# New_Schematic.net
KiCad netlist of a schematic drawn in EAGLE
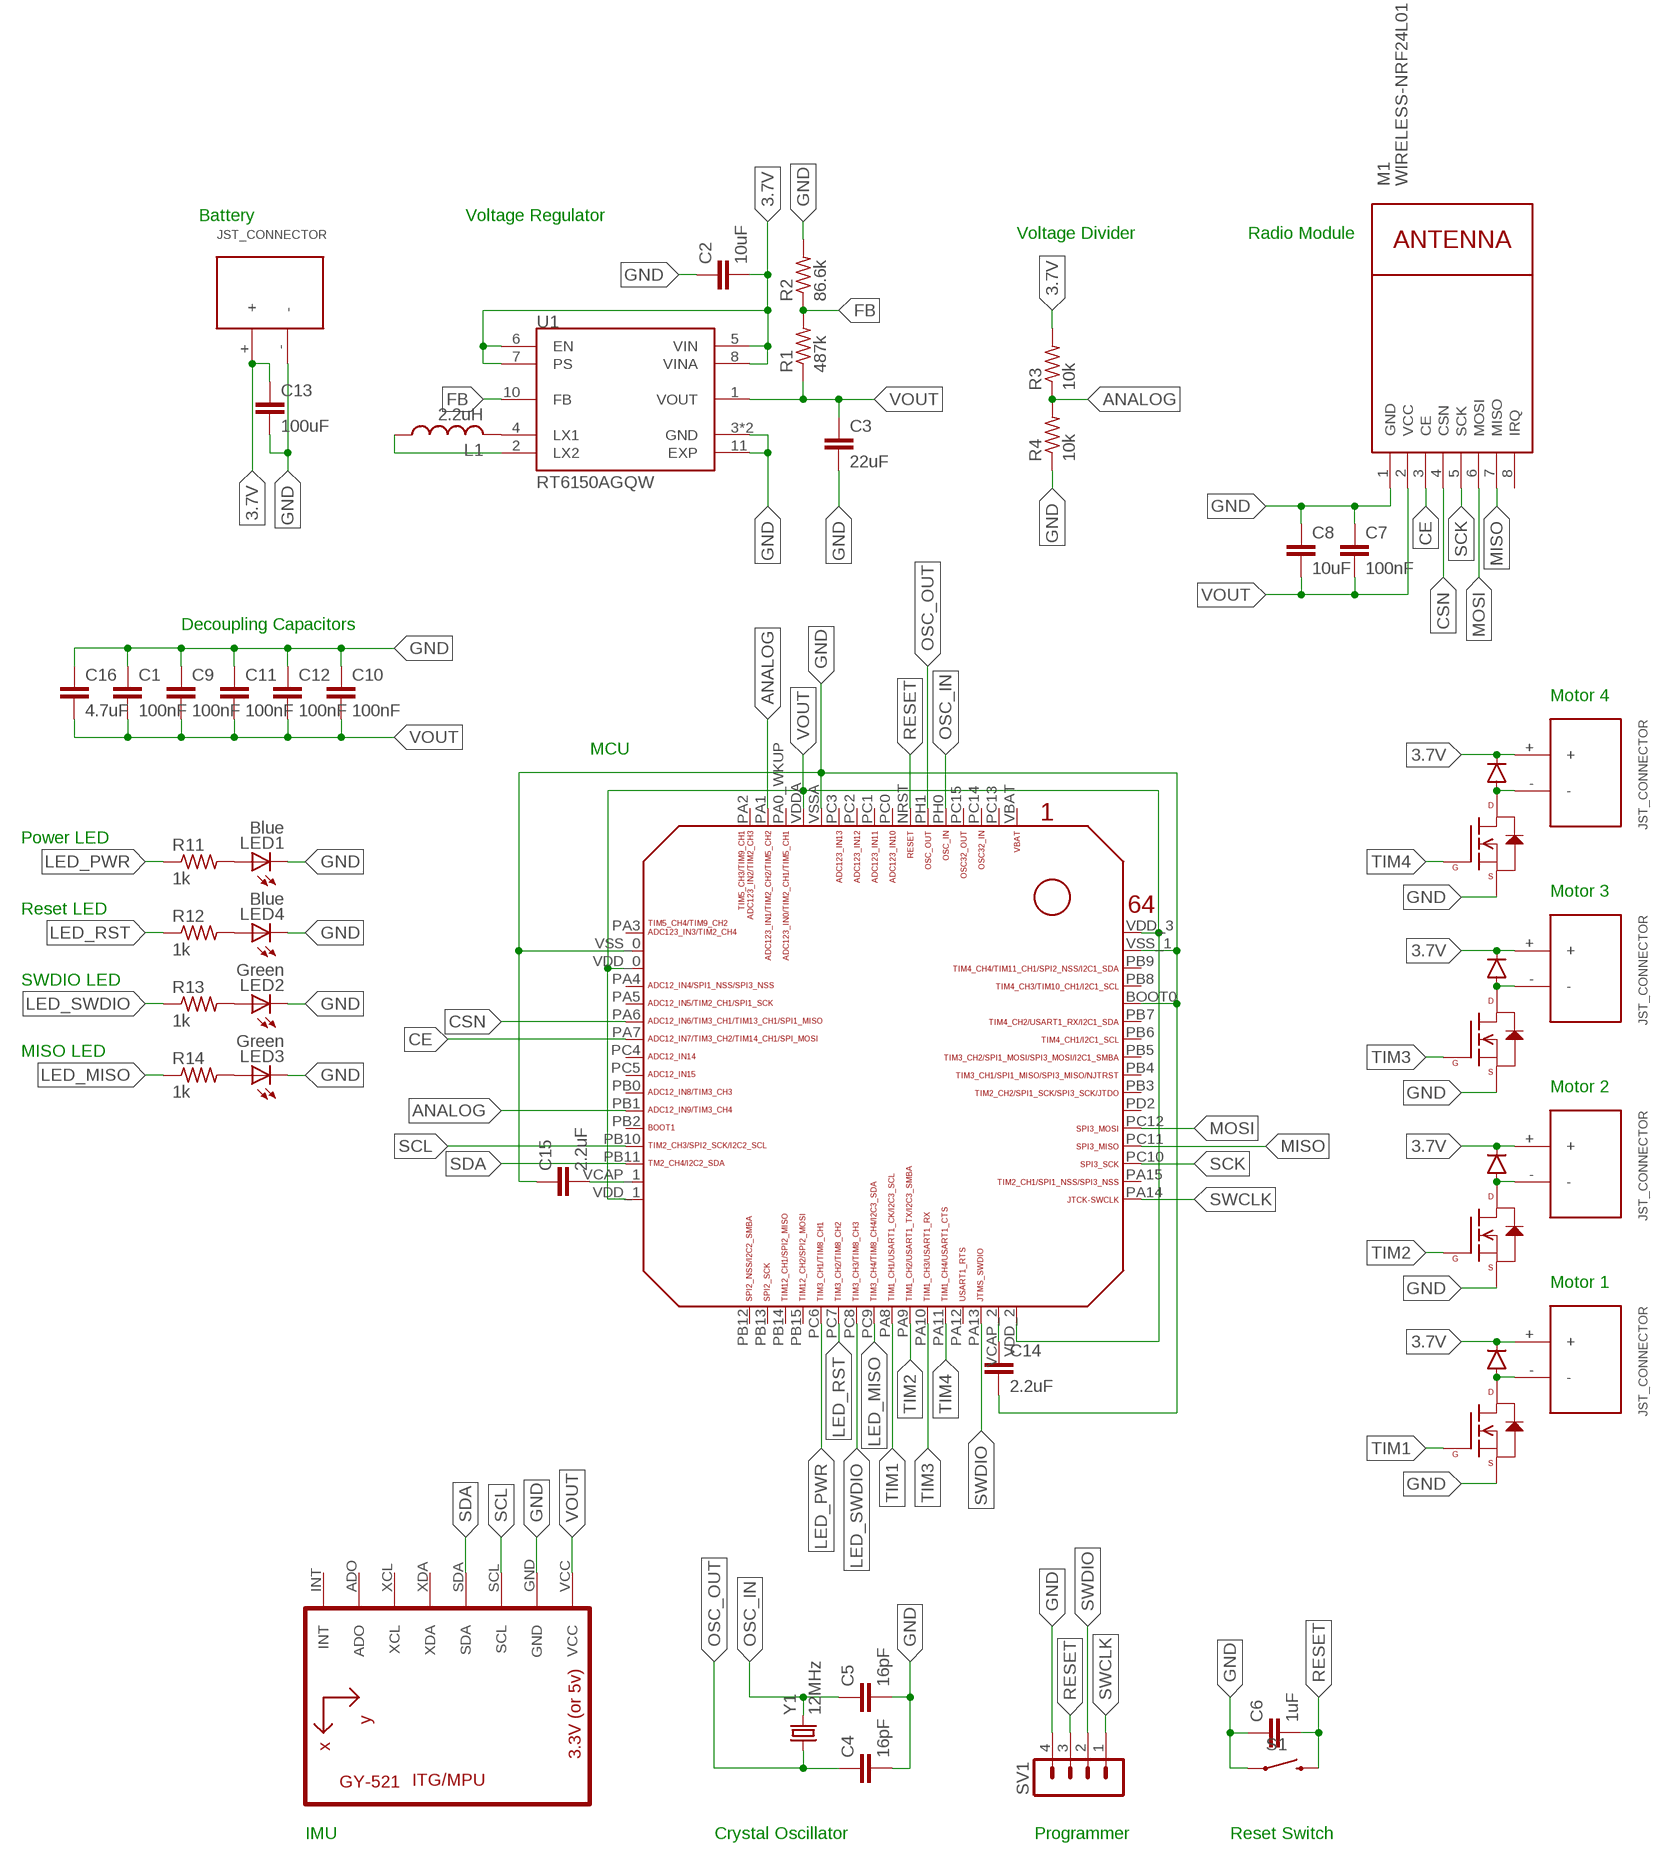
[diagram p0: schematic, sheet 1]

(export (version "E")
  (design (tool "Eeschema 10.0.6"))
  (components
    (comp (ref "C1")
      (value "100nF")
      (footprint "eagle-import:C0603")
      (libsource (lib "eagle-import") (part "rcl_334_C-EUC0603"))
    )
    (comp (ref "C2")
      (value "10uF")
      (footprint "eagle-import:C0603")
      (libsource (lib "eagle-import") (part "rcl_334_C-EUC0603"))
    )
    (comp (ref "C3")
      (value "22uF")
      (footprint "eagle-import:C0603")
      (libsource (lib "eagle-import") (part "rcl_334_C-EUC0603"))
    )
    (comp (ref "C4")
      (value "16pF")
      (footprint "eagle-import:C0603")
      (libsource (lib "eagle-import") (part "rcl_334_C-EUC0603"))
    )
    (comp (ref "C5")
      (value "16pF")
      (footprint "eagle-import:C0603")
      (libsource (lib "eagle-import") (part "rcl_334_C-EUC0603"))
    )
    (comp (ref "C6")
      (value "1uF")
      (footprint "eagle-import:C0603")
      (libsource (lib "eagle-import") (part "rcl_334_C-EUC0603"))
    )
    (comp (ref "C7")
      (value "100nF")
      (footprint "eagle-import:C0603")
      (libsource (lib "eagle-import") (part "rcl_334_C-EUC0603"))
    )
    (comp (ref "C8")
      (value "10uF")
      (footprint "eagle-import:C0603")
      (libsource (lib "eagle-import") (part "rcl_334_C-EUC0603"))
    )
    (comp (ref "C9")
      (value "100nF")
      (footprint "eagle-import:C0603")
      (libsource (lib "eagle-import") (part "rcl_334_C-EUC0603"))
    )
    (comp (ref "C10")
      (value "100nF")
      (footprint "eagle-import:C0603")
      (libsource (lib "eagle-import") (part "rcl_334_C-EUC0603"))
    )
    (comp (ref "C11")
      (value "100nF")
      (footprint "eagle-import:C0603")
      (libsource (lib "eagle-import") (part "rcl_334_C-EUC0603"))
    )
    (comp (ref "C12")
      (value "100nF")
      (footprint "eagle-import:C0603")
      (libsource (lib "eagle-import") (part "rcl_334_C-EUC0603"))
    )
    (comp (ref "C13")
      (value "100uF")
      (footprint "eagle-import:C1206")
      (libsource (lib "eagle-import") (part "rcl_334_C-EUC1206"))
    )
    (comp (ref "C14")
      (value "2.2uF")
      (footprint "eagle-import:C0603")
      (libsource (lib "eagle-import") (part "C-EUC0603"))
    )
    (comp (ref "C15")
      (value "2.2uF")
      (footprint "eagle-import:C0603")
      (libsource (lib "eagle-import") (part "C-EUC0603"))
    )
    (comp (ref "C16")
      (value "4.7uF")
      (footprint "eagle-import:C0603")
      (libsource (lib "eagle-import") (part "rcl_334_C-EUC0603"))
    )
    (comp (ref "L1")
      (value "2.2uH")
      (footprint "eagle-import:L0603")
      (libsource (lib "eagle-import") (part "L-USL0603"))
    )
    (comp (ref "LED1")
      (value "Blue")
      (footprint "eagle-import:CHIP-LED0603")
      (libsource (lib "eagle-import") (part "LEDCHIP-LED0603"))
    )
    (comp (ref "LED2")
      (value "Green")
      (footprint "eagle-import:CHIP-LED0603")
      (libsource (lib "eagle-import") (part "LEDCHIP-LED0603"))
    )
    (comp (ref "LED3")
      (value "Green")
      (footprint "eagle-import:CHIP-LED0603")
      (libsource (lib "eagle-import") (part "LEDCHIP-LED0603"))
    )
    (comp (ref "LED4")
      (value "Blue")
      (footprint "eagle-import:CHIP-LED0603")
      (libsource (lib "eagle-import") (part "LEDCHIP-LED0603"))
    )
    (comp (ref "M1")
      (value "WIRELESS-NRF24L01")
      (footprint "eagle-import:WIRELESS-NRF24L01")
      (libsource (lib "eagle-import") (part "WIRELESS-NRF24L01"))
    )
    (comp (ref "R1")
      (value "487k")
      (footprint "eagle-import:R0603")
      (libsource (lib "eagle-import") (part "R-US_R0603"))
    )
    (comp (ref "R2")
      (value "86.6k")
      (footprint "eagle-import:R0603")
      (libsource (lib "eagle-import") (part "R-US_R0603"))
    )
    (comp (ref "R3")
      (value "10k")
      (footprint "eagle-import:R0603")
      (libsource (lib "eagle-import") (part "R-US_R0603"))
    )
    (comp (ref "R4")
      (value "10k")
      (footprint "eagle-import:R0603")
      (libsource (lib "eagle-import") (part "R-US_R0603"))
    )
    (comp (ref "R11")
      (value "1k")
      (footprint "eagle-import:R0603")
      (libsource (lib "eagle-import") (part "R-US_R0603"))
    )
    (comp (ref "R12")
      (value "1k")
      (footprint "eagle-import:R0603")
      (libsource (lib "eagle-import") (part "R-US_R0603"))
    )
    (comp (ref "R13")
      (value "1k")
      (footprint "eagle-import:R0603")
      (libsource (lib "eagle-import") (part "R-US_R0603"))
    )
    (comp (ref "R14")
      (value "1k")
      (footprint "eagle-import:R0603")
      (libsource (lib "eagle-import") (part "R-US_R0603"))
    )
    (comp (ref "S1")
      (value "SWITCH-MOMENTARY-2SMD")
      (footprint "eagle-import:TACTILE-SWITCH-SMD")
      (libsource (lib "eagle-import") (part "SWITCH-MOMENTARY-2SMD"))
    )
    (comp (ref "SV1")
      (value "MA04-1")
      (footprint "eagle-import:MA04-1")
      (libsource (lib "eagle-import") (part "MA04-1"))
    )
    (comp (ref "U$1")
      (value "STM32F405/415_LQFP64")
      (footprint "eagle-import:STM32F405_415_LQFP64")
      (libsource (lib "eagle-import") (part "STM32F405/415_LQFP64"))
    )
    (comp (ref "U$2")
      (value "JST_CONNECTOR_FEMALE")
      (footprint "eagle-import:JST_CONNECTOR_FEMALE")
      (libsource (lib "eagle-import") (part "JST_CONNECTOR_FEMALE"))
    )
    (comp (ref "U$3")
      (value "JST_CONNECTOR_FEMALE")
      (footprint "eagle-import:JST_CONNECTOR_FEMALE")
      (libsource (lib "eagle-import") (part "JST_CONNECTOR_FEMALE"))
    )
    (comp (ref "U$4")
      (value "JST_CONNECTOR_FEMALE")
      (footprint "eagle-import:JST_CONNECTOR_FEMALE")
      (libsource (lib "eagle-import") (part "JST_CONNECTOR_FEMALE"))
    )
    (comp (ref "U$5")
      (value "JST_CONNECTOR_FEMALE")
      (footprint "eagle-import:JST_CONNECTOR_FEMALE")
      (libsource (lib "eagle-import") (part "JST_CONNECTOR_FEMALE"))
    )
    (comp (ref "U$6")
      (value "JST_CONNECTOR_FEMALE")
      (footprint "eagle-import:JST_CONNECTOR_FEMALE")
      (libsource (lib "eagle-import") (part "JST_CONNECTOR_FEMALE"))
    )
    (comp (ref "U$7")
      (value "N-CHANNEL-MOSFET-IRLML6244TRPBF")
      (footprint "eagle-import:SOT23-3")
      (libsource (lib "eagle-import") (part "N-CHANNEL-MOSFET-IRLML6244TRPBF"))
    )
    (comp (ref "U$8")
      (value "N-CHANNEL-MOSFET-IRLML6244TRPBF")
      (footprint "eagle-import:SOT23-3")
      (libsource (lib "eagle-import") (part "N-CHANNEL-MOSFET-IRLML6244TRPBF"))
    )
    (comp (ref "U$9")
      (value "N-CHANNEL-MOSFET-IRLML6244TRPBF")
      (footprint "eagle-import:SOT23-3")
      (libsource (lib "eagle-import") (part "N-CHANNEL-MOSFET-IRLML6244TRPBF"))
    )
    (comp (ref "U$10")
      (value "N-CHANNEL-MOSFET-IRLML6244TRPBF")
      (footprint "eagle-import:SOT23-3")
      (libsource (lib "eagle-import") (part "N-CHANNEL-MOSFET-IRLML6244TRPBF"))
    )
    (comp (ref "U$11")
      (value "DB2W40300L")
      (footprint "eagle-import:MINI2-F3-B")
      (libsource (lib "eagle-import") (part "DB2W40300L"))
    )
    (comp (ref "U$12")
      (value "DB2W40300L")
      (footprint "eagle-import:MINI2-F3-B")
      (libsource (lib "eagle-import") (part "DB2W40300L"))
    )
    (comp (ref "U$13")
      (value "DB2W40300L")
      (footprint "eagle-import:MINI2-F3-B")
      (libsource (lib "eagle-import") (part "DB2W40300L"))
    )
    (comp (ref "U$14")
      (value "DB2W40300L")
      (footprint "eagle-import:MINI2-F3-B")
      (libsource (lib "eagle-import") (part "DB2W40300L"))
    )
    (comp (ref "U1")
      (value "RT6150AGQW")
      (footprint "eagle-import:SON50P250X250X80-11N")
      (fields (field (name "MF") "Richtek USA"))
      (libsource (lib "eagle-import") (part "RT6150AGQW"))
    )
    (comp (ref "U2")
      (value "GY-521MPU6050")
      (footprint "eagle-import:GY-521")
      (libsource (lib "eagle-import") (part "GY-521MPU6050"))
    )
    (comp (ref "Y1")
      (value "12MHz")
      (footprint "eagle-import:HC49US")
      (libsource (lib "eagle-import") (part "CRYSTALHC49US"))
    )
  )
  (nets
    (net (code "1") (name "3.7V") (class "Default")
      (node (ref "C13") (pin "1") (pinfunction "1_1") (pintype "passive"))
      (node (ref "C2") (pin "2") (pinfunction "2_2") (pintype "passive"))
      (node (ref "R3") (pin "2") (pinfunction "2_2") (pintype "passive"))
      (node (ref "U$11") (pin "NEG") (pinfunction "GPIN_NEG") (pintype "passive"))
      (node (ref "U$12") (pin "NEG") (pinfunction "GPIN_NEG") (pintype "passive"))
      (node (ref "U$13") (pin "NEG") (pinfunction "GPIN_NEG") (pintype "passive"))
      (node (ref "U$14") (pin "NEG") (pinfunction "GPIN_NEG") (pintype "passive"))
      (node (ref "U$2") (pin "+") (pinfunction "+_+") (pintype "bidirectional"))
      (node (ref "U$3") (pin "+") (pinfunction "+_+") (pintype "bidirectional"))
      (node (ref "U$4") (pin "+") (pinfunction "+_+") (pintype "bidirectional"))
      (node (ref "U$5") (pin "+") (pinfunction "+_+") (pintype "bidirectional"))
      (node (ref "U$6") (pin "+") (pinfunction "+_+") (pintype "bidirectional"))
      (node (ref "U1") (pin "5") (pinfunction "VIN_5") (pintype "power_in"))
      (node (ref "U1") (pin "6") (pinfunction "EN_6") (pintype "input"))
      (node (ref "U1") (pin "7") (pinfunction "PS_7") (pintype "input"))
      (node (ref "U1") (pin "8") (pinfunction "VINA_8") (pintype "power_in"))
    )
    (net (code "2") (name "ANALOG") (class "Default")
      (node (ref "R3") (pin "1") (pinfunction "1_1") (pintype "passive"))
      (node (ref "R4") (pin "2") (pinfunction "2_2") (pintype "passive"))
      (node (ref "U$1") (pin "PA1") (pinfunction "PA1_PA1") (pintype "bidirectional"))
      (node (ref "U$1") (pin "PB1") (pinfunction "PB1_PB1") (pintype "bidirectional"))
    )
    (net (code "3") (name "CE") (class "Default")
      (node (ref "M1") (pin "3") (pinfunction "CE_3") (pintype "bidirectional"))
      (node (ref "U$1") (pin "PA7") (pinfunction "PA7_PA7") (pintype "bidirectional"))
    )
    (net (code "4") (name "CSN") (class "Default")
      (node (ref "M1") (pin "4") (pinfunction "CSN_4") (pintype "bidirectional"))
      (node (ref "U$1") (pin "PA6") (pinfunction "PA6_PA6") (pintype "bidirectional"))
    )
    (net (code "5") (name "FB") (class "Default")
      (node (ref "R1") (pin "2") (pinfunction "2_2") (pintype "passive"))
      (node (ref "R2") (pin "1") (pinfunction "1_1") (pintype "passive"))
      (node (ref "U1") (pin "10") (pinfunction "FB_10") (pintype "input"))
    )
    (net (code "6") (name "GND") (class "Default")
      (node (ref "C1") (pin "1") (pinfunction "1_1") (pintype "passive"))
      (node (ref "C10") (pin "1") (pinfunction "1_1") (pintype "passive"))
      (node (ref "C11") (pin "1") (pinfunction "1_1") (pintype "passive"))
      (node (ref "C12") (pin "1") (pinfunction "1_1") (pintype "passive"))
      (node (ref "C13") (pin "2") (pinfunction "2_2") (pintype "passive"))
      (node (ref "C14") (pin "2") (pinfunction "2_2") (pintype "passive"))
      (node (ref "C15") (pin "1") (pinfunction "1_1") (pintype "passive"))
      (node (ref "C16") (pin "1") (pinfunction "1_1") (pintype "passive"))
      (node (ref "C2") (pin "1") (pinfunction "1_1") (pintype "passive"))
      (node (ref "C3") (pin "2") (pinfunction "2_2") (pintype "passive"))
      (node (ref "C4") (pin "2") (pinfunction "2_2") (pintype "passive"))
      (node (ref "C5") (pin "2") (pinfunction "2_2") (pintype "passive"))
      (node (ref "C6") (pin "1") (pinfunction "1_1") (pintype "passive"))
      (node (ref "C7") (pin "1") (pinfunction "1_1") (pintype "passive"))
      (node (ref "C8") (pin "1") (pinfunction "1_1") (pintype "passive"))
      (node (ref "C9") (pin "1") (pinfunction "1_1") (pintype "passive"))
      (node (ref "LED1") (pin "C") (pinfunction "C_C") (pintype "passive"))
      (node (ref "LED2") (pin "C") (pinfunction "C_C") (pintype "passive"))
      (node (ref "LED3") (pin "C") (pinfunction "C_C") (pintype "passive"))
      (node (ref "LED4") (pin "C") (pinfunction "C_C") (pintype "passive"))
      (node (ref "M1") (pin "1") (pinfunction "GND_1") (pintype "power_in"))
      (node (ref "R2") (pin "2") (pinfunction "2_2") (pintype "passive"))
      (node (ref "R4") (pin "1") (pinfunction "1_1") (pintype "passive"))
      (node (ref "S1") (pin "1") (pinfunction "1_1") (pintype "passive"))
      (node (ref "SV1") (pin "4") (pinfunction "4_4") (pintype "passive"))
      (node (ref "U$1") (pin "BOOT0") (pinfunction "BOOT0_BOOT0") (pintype "bidirectional"))
      (node (ref "U$1") (pin "VSSA") (pinfunction "VSSA_VSSA") (pintype "bidirectional"))
      (node (ref "U$1") (pin "VSS_0") (pinfunction "VSS_0_VSS_0") (pintype "bidirectional"))
      (node (ref "U$1") (pin "VSS_1") (pinfunction "VSS_1_VSS_1") (pintype "bidirectional"))
      (node (ref "U$10") (pin "2") (pinfunction "S_2") (pintype "passive"))
      (node (ref "U$2") (pin "-") (pinfunction "-_-") (pintype "bidirectional"))
      (node (ref "U$7") (pin "2") (pinfunction "S_2") (pintype "passive"))
      (node (ref "U$8") (pin "2") (pinfunction "S_2") (pintype "passive"))
      (node (ref "U$9") (pin "2") (pinfunction "S_2") (pintype "passive"))
      (node (ref "U1") (pin "11") (pinfunction "EXP_11") (pintype "passive"))
      (node (ref "U1") (pin "3") (pinfunction "GND_3") (pintype "power_in"))
      (node (ref "U1") (pin "9") (pinfunction "GND_9") (pintype "power_in"))
      (node (ref "U2") (pin "GND") (pinfunction "GND_GND") (pintype "bidirectional"))
    )
    (net (code "7") (name "LED_MISO") (class "Default")
      (node (ref "R14") (pin "1") (pinfunction "1_1") (pintype "passive"))
      (node (ref "U$1") (pin "PC9") (pinfunction "PC9_PC9") (pintype "bidirectional"))
    )
    (net (code "8") (name "LED_PWR") (class "Default")
      (node (ref "R11") (pin "1") (pinfunction "1_1") (pintype "passive"))
      (node (ref "U$1") (pin "PC6") (pinfunction "PC6_PC6") (pintype "bidirectional"))
    )
    (net (code "9") (name "LED_RST") (class "Default")
      (node (ref "R12") (pin "1") (pinfunction "1_1") (pintype "passive"))
      (node (ref "U$1") (pin "PC7") (pinfunction "PC7_PC7") (pintype "bidirectional"))
    )
    (net (code "10") (name "LED_SWDIO") (class "Default")
      (node (ref "R13") (pin "1") (pinfunction "1_1") (pintype "passive"))
      (node (ref "U$1") (pin "PC8") (pinfunction "PC8_PC8") (pintype "bidirectional"))
    )
    (net (code "11") (name "MISO") (class "Default")
      (node (ref "M1") (pin "7") (pinfunction "MISO_7") (pintype "bidirectional"))
      (node (ref "U$1") (pin "PC11") (pinfunction "PC11_PC11") (pintype "bidirectional"))
    )
    (net (code "12") (name "MOSI") (class "Default")
      (node (ref "M1") (pin "6") (pinfunction "MOSI_6") (pintype "bidirectional"))
      (node (ref "U$1") (pin "PC12") (pinfunction "PC12_PC12") (pintype "bidirectional"))
    )
    (net (code "13") (name "Net-(C14-Pad1)") (class "Default")
      (node (ref "C14") (pin "1") (pinfunction "1_1") (pintype "passive"))
      (node (ref "U$1") (pin "VCAP_2") (pinfunction "VCAP_2_VCAP_2") (pintype "bidirectional"))
    )
    (net (code "14") (name "Net-(C15-Pad2)") (class "Default")
      (node (ref "C15") (pin "2") (pinfunction "2_2") (pintype "passive"))
      (node (ref "U$1") (pin "VCAP_1") (pinfunction "VCAP_1_VCAP_1") (pintype "bidirectional"))
    )
    (net (code "15") (name "Net-(LED1-PadA)") (class "Default")
      (node (ref "LED1") (pin "A") (pinfunction "A_A") (pintype "passive"))
      (node (ref "R11") (pin "2") (pinfunction "2_2") (pintype "passive"))
    )
    (net (code "16") (name "Net-(LED2-PadA)") (class "Default")
      (node (ref "LED2") (pin "A") (pinfunction "A_A") (pintype "passive"))
      (node (ref "R13") (pin "2") (pinfunction "2_2") (pintype "passive"))
    )
    (net (code "17") (name "Net-(LED3-PadA)") (class "Default")
      (node (ref "LED3") (pin "A") (pinfunction "A_A") (pintype "passive"))
      (node (ref "R14") (pin "2") (pinfunction "2_2") (pintype "passive"))
    )
    (net (code "18") (name "Net-(LED4-PadA)") (class "Default")
      (node (ref "LED4") (pin "A") (pinfunction "A_A") (pintype "passive"))
      (node (ref "R12") (pin "2") (pinfunction "2_2") (pintype "passive"))
    )
    (net (code "19") (name "Net-(U$10-D)") (class "Default")
      (node (ref "U$10") (pin "3") (pinfunction "D_3") (pintype "passive"))
      (node (ref "U$14") (pin "POS") (pinfunction "PPIN_POS") (pintype "passive"))
      (node (ref "U$6") (pin "-") (pinfunction "-_-") (pintype "bidirectional"))
    )
    (net (code "20") (name "Net-(U$11-PPIN)") (class "Default")
      (node (ref "U$11") (pin "POS") (pinfunction "PPIN_POS") (pintype "passive"))
      (node (ref "U$3") (pin "-") (pinfunction "-_-") (pintype "bidirectional"))
      (node (ref "U$9") (pin "3") (pinfunction "D_3") (pintype "passive"))
    )
    (net (code "21") (name "Net-(U$12-PPIN)") (class "Default")
      (node (ref "U$12") (pin "POS") (pinfunction "PPIN_POS") (pintype "passive"))
      (node (ref "U$5") (pin "-") (pinfunction "-_-") (pintype "bidirectional"))
      (node (ref "U$8") (pin "3") (pinfunction "D_3") (pintype "passive"))
    )
    (net (code "22") (name "Net-(U$13-PPIN)") (class "Default")
      (node (ref "U$13") (pin "POS") (pinfunction "PPIN_POS") (pintype "passive"))
      (node (ref "U$4") (pin "-") (pinfunction "-_-") (pintype "bidirectional"))
      (node (ref "U$7") (pin "3") (pinfunction "D_3") (pintype "passive"))
    )
    (net (code "23") (name "Net-(U1-LX1)") (class "Default")
      (node (ref "L1") (pin "2") (pinfunction "2_2") (pintype "passive"))
      (node (ref "U1") (pin "4") (pinfunction "LX1_4") (pintype "passive"))
    )
    (net (code "24") (name "Net-(U1-LX2)") (class "Default")
      (node (ref "L1") (pin "1") (pinfunction "1_1") (pintype "passive"))
      (node (ref "U1") (pin "2") (pinfunction "LX2_2") (pintype "passive"))
    )
    (net (code "25") (name "OSC_IN") (class "Default")
      (node (ref "C5") (pin "1") (pinfunction "1_1") (pintype "passive"))
      (node (ref "U$1") (pin "PH0") (pinfunction "PH0_PH0") (pintype "bidirectional"))
      (node (ref "Y1") (pin "2") (pinfunction "2_2") (pintype "passive"))
    )
    (net (code "26") (name "OSC_OUT") (class "Default")
      (node (ref "C4") (pin "1") (pinfunction "1_1") (pintype "passive"))
      (node (ref "U$1") (pin "PH1") (pinfunction "PH1_PH1") (pintype "bidirectional"))
      (node (ref "Y1") (pin "1") (pinfunction "1_1") (pintype "passive"))
    )
    (net (code "27") (name "RESET") (class "Default")
      (node (ref "C6") (pin "2") (pinfunction "2_2") (pintype "passive"))
      (node (ref "S1") (pin "3") (pinfunction "2_3") (pintype "passive"))
      (node (ref "SV1") (pin "3") (pinfunction "3_3") (pintype "passive"))
      (node (ref "U$1") (pin "NRST") (pinfunction "NRST_NRST") (pintype "bidirectional"))
    )
    (net (code "28") (name "SCK") (class "Default")
      (node (ref "M1") (pin "5") (pinfunction "SCK_5") (pintype "bidirectional"))
      (node (ref "U$1") (pin "PC10") (pinfunction "PC10_PC10") (pintype "bidirectional"))
    )
    (net (code "29") (name "SCL") (class "Default")
      (node (ref "U$1") (pin "PB10") (pinfunction "PB10_PB10") (pintype "bidirectional"))
      (node (ref "U2") (pin "SCL") (pinfunction "SCL_SCL") (pintype "bidirectional"))
    )
    (net (code "30") (name "SDA") (class "Default")
      (node (ref "U$1") (pin "PB11") (pinfunction "PB11_PB11") (pintype "bidirectional"))
      (node (ref "U2") (pin "SDA") (pinfunction "SDA_SDA") (pintype "bidirectional"))
    )
    (net (code "31") (name "SWCLK") (class "Default")
      (node (ref "SV1") (pin "1") (pinfunction "1_1") (pintype "passive"))
      (node (ref "U$1") (pin "PA14") (pinfunction "PA14_PA14") (pintype "bidirectional"))
    )
    (net (code "32") (name "SWDIO") (class "Default")
      (node (ref "SV1") (pin "2") (pinfunction "2_2") (pintype "passive"))
      (node (ref "U$1") (pin "PA13") (pinfunction "PA13_PA13") (pintype "bidirectional"))
    )
    (net (code "33") (name "TIM1") (class "Default")
      (node (ref "U$1") (pin "PA8") (pinfunction "PA8_PA8") (pintype "bidirectional"))
      (node (ref "U$10") (pin "1") (pinfunction "G_1") (pintype "passive"))
    )
    (net (code "34") (name "TIM2") (class "Default")
      (node (ref "U$1") (pin "PA9") (pinfunction "PA9_PA9") (pintype "bidirectional"))
      (node (ref "U$8") (pin "1") (pinfunction "G_1") (pintype "passive"))
    )
    (net (code "35") (name "TIM3") (class "Default")
      (node (ref "U$1") (pin "PA10") (pinfunction "PA10_PA10") (pintype "bidirectional"))
      (node (ref "U$7") (pin "1") (pinfunction "G_1") (pintype "passive"))
    )
    (net (code "36") (name "TIM4") (class "Default")
      (node (ref "U$1") (pin "PA11") (pinfunction "PA11_PA11") (pintype "bidirectional"))
      (node (ref "U$9") (pin "1") (pinfunction "G_1") (pintype "passive"))
    )
    (net (code "37") (name "VOUT") (class "Default")
      (node (ref "C1") (pin "2") (pinfunction "2_2") (pintype "passive"))
      (node (ref "C10") (pin "2") (pinfunction "2_2") (pintype "passive"))
      (node (ref "C11") (pin "2") (pinfunction "2_2") (pintype "passive"))
      (node (ref "C12") (pin "2") (pinfunction "2_2") (pintype "passive"))
      (node (ref "C16") (pin "2") (pinfunction "2_2") (pintype "passive"))
      (node (ref "C3") (pin "1") (pinfunction "1_1") (pintype "passive"))
      (node (ref "C7") (pin "2") (pinfunction "2_2") (pintype "passive"))
      (node (ref "C8") (pin "2") (pinfunction "2_2") (pintype "passive"))
      (node (ref "C9") (pin "2") (pinfunction "2_2") (pintype "passive"))
      (node (ref "M1") (pin "2") (pinfunction "VCC_2") (pintype "power_in"))
      (node (ref "R1") (pin "1") (pinfunction "1_1") (pintype "passive"))
      (node (ref "U$1") (pin "VDDA") (pinfunction "VDDA_VDDA") (pintype "bidirectional"))
      (node (ref "U$1") (pin "VDD_0") (pinfunction "VDD_0_VDD_0") (pintype "bidirectional"))
      (node (ref "U$1") (pin "VDD_1") (pinfunction "VDD_1_VDD_1") (pintype "bidirectional"))
      (node (ref "U$1") (pin "VDD_2") (pinfunction "VDD_2_VDD_2") (pintype "bidirectional"))
      (node (ref "U$1") (pin "VDD_3") (pinfunction "VDD_3_VDD_3") (pintype "bidirectional"))
      (node (ref "U1") (pin "1") (pinfunction "VOUT_1") (pintype "output"))
      (node (ref "U2") (pin "VCC") (pinfunction "VCC_VCC") (pintype "bidirectional"))
    )
    (net (code "38") (name "unconnected-(M1-IRQ-Pad8)") (class "Default")
      (node (ref "M1") (pin "8") (pinfunction "IRQ_8") (pintype "bidirectional"))
    )
    (net (code "39") (name "unconnected-(U$1-PA0_AKUP-PadPA0_WKUP)") (class "Default")
      (node (ref "U$1") (pin "PA0_WKUP") (pinfunction "PA0_AKUP_PA0_WKUP") (pintype "bidirectional"))
    )
    (net (code "40") (name "unconnected-(U$1-PadPA2)") (class "Default")
      (node (ref "U$1") (pin "PA2") (pinfunction "PA2_PA2") (pintype "bidirectional"))
    )
    (net (code "41") (name "unconnected-(U$1-PadPA3)") (class "Default")
      (node (ref "U$1") (pin "PA3") (pinfunction "PA3_PA3") (pintype "bidirectional"))
    )
    (net (code "42") (name "unconnected-(U$1-PadPA4)") (class "Default")
      (node (ref "U$1") (pin "PA4") (pinfunction "PA4_PA4") (pintype "bidirectional"))
    )
    (net (code "43") (name "unconnected-(U$1-PadPA5)") (class "Default")
      (node (ref "U$1") (pin "PA5") (pinfunction "PA5_PA5") (pintype "bidirectional"))
    )
    (net (code "44") (name "unconnected-(U$1-PadPA12)") (class "Default")
      (node (ref "U$1") (pin "PA12") (pinfunction "PA12_PA12") (pintype "bidirectional"))
    )
    (net (code "45") (name "unconnected-(U$1-PadPA15)") (class "Default")
      (node (ref "U$1") (pin "PA15") (pinfunction "PA15_PA15") (pintype "bidirectional"))
    )
    (net (code "46") (name "unconnected-(U$1-PadPB0)") (class "Default")
      (node (ref "U$1") (pin "PB0") (pinfunction "PB0_PB0") (pintype "bidirectional"))
    )
    (net (code "47") (name "unconnected-(U$1-PadPB2)") (class "Default")
      (node (ref "U$1") (pin "PB2") (pinfunction "PB2_PB2") (pintype "bidirectional"))
    )
    (net (code "48") (name "unconnected-(U$1-PadPB3)") (class "Default")
      (node (ref "U$1") (pin "PB3") (pinfunction "PB3_PB3") (pintype "bidirectional"))
    )
    (net (code "49") (name "unconnected-(U$1-PadPB4)") (class "Default")
      (node (ref "U$1") (pin "PB4") (pinfunction "PB4_PB4") (pintype "bidirectional"))
    )
    (net (code "50") (name "unconnected-(U$1-PadPB5)") (class "Default")
      (node (ref "U$1") (pin "PB5") (pinfunction "PB5_PB5") (pintype "bidirectional"))
    )
    (net (code "51") (name "unconnected-(U$1-PadPB6)") (class "Default")
      (node (ref "U$1") (pin "PB6") (pinfunction "PB6_PB6") (pintype "bidirectional"))
    )
    (net (code "52") (name "unconnected-(U$1-PadPB7)") (class "Default")
      (node (ref "U$1") (pin "PB7") (pinfunction "PB7_PB7") (pintype "bidirectional"))
    )
    (net (code "53") (name "unconnected-(U$1-PadPB8)") (class "Default")
      (node (ref "U$1") (pin "PB8") (pinfunction "PB8_PB8") (pintype "bidirectional"))
    )
    (net (code "54") (name "unconnected-(U$1-PadPB9)") (class "Default")
      (node (ref "U$1") (pin "PB9") (pinfunction "PB9_PB9") (pintype "bidirectional"))
    )
    (net (code "55") (name "unconnected-(U$1-PadPB12)") (class "Default")
      (node (ref "U$1") (pin "PB12") (pinfunction "PB12_PB12") (pintype "bidirectional"))
    )
    (net (code "56") (name "unconnected-(U$1-PadPB13)") (class "Default")
      (node (ref "U$1") (pin "PB13") (pinfunction "PB13_PB13") (pintype "bidirectional"))
    )
    (net (code "57") (name "unconnected-(U$1-PadPB14)") (class "Default")
      (node (ref "U$1") (pin "PB14") (pinfunction "PB14_PB14") (pintype "bidirectional"))
    )
    (net (code "58") (name "unconnected-(U$1-PadPB15)") (class "Default")
      (node (ref "U$1") (pin "PB15") (pinfunction "PB15_PB15") (pintype "bidirectional"))
    )
    (net (code "59") (name "unconnected-(U$1-PadPC0)") (class "Default")
      (node (ref "U$1") (pin "PC0") (pinfunction "PC0_PC0") (pintype "bidirectional"))
    )
    (net (code "60") (name "unconnected-(U$1-PadPC1)") (class "Default")
      (node (ref "U$1") (pin "PC1") (pinfunction "PC1_PC1") (pintype "bidirectional"))
    )
    (net (code "61") (name "unconnected-(U$1-PadPC2)") (class "Default")
      (node (ref "U$1") (pin "PC2") (pinfunction "PC2_PC2") (pintype "bidirectional"))
    )
    (net (code "62") (name "unconnected-(U$1-PadPC3)") (class "Default")
      (node (ref "U$1") (pin "PC3") (pinfunction "PC3_PC3") (pintype "bidirectional"))
    )
    (net (code "63") (name "unconnected-(U$1-PadPC4)") (class "Default")
      (node (ref "U$1") (pin "PC4") (pinfunction "PC4_PC4") (pintype "bidirectional"))
    )
    (net (code "64") (name "unconnected-(U$1-PadPC5)") (class "Default")
      (node (ref "U$1") (pin "PC5") (pinfunction "PC5_PC5") (pintype "bidirectional"))
    )
    (net (code "65") (name "unconnected-(U$1-PadPC13)") (class "Default")
      (node (ref "U$1") (pin "PC13") (pinfunction "PC13_PC13") (pintype "bidirectional"))
    )
    (net (code "66") (name "unconnected-(U$1-PadPC14)") (class "Default")
      (node (ref "U$1") (pin "PC14") (pinfunction "PC14_PC14") (pintype "bidirectional"))
    )
    (net (code "67") (name "unconnected-(U$1-PadPC15)") (class "Default")
      (node (ref "U$1") (pin "PC15") (pinfunction "PC15_PC15") (pintype "bidirectional"))
    )
    (net (code "68") (name "unconnected-(U$1-PadPD2)") (class "Default")
      (node (ref "U$1") (pin "PD2") (pinfunction "PD2_PD2") (pintype "bidirectional"))
    )
    (net (code "69") (name "unconnected-(U$1-PadVBAT)") (class "Default")
      (node (ref "U$1") (pin "VBAT") (pinfunction "VBAT_VBAT") (pintype "bidirectional"))
    )
    (net (code "70") (name "unconnected-(U2-PadADO)") (class "Default")
      (node (ref "U2") (pin "ADO") (pinfunction "ADO_ADO") (pintype "bidirectional"))
    )
    (net (code "71") (name "unconnected-(U2-PadINT)") (class "Default")
      (node (ref "U2") (pin "INT") (pinfunction "INT_INT") (pintype "bidirectional"))
    )
    (net (code "72") (name "unconnected-(U2-PadXCL)") (class "Default")
      (node (ref "U2") (pin "XCL") (pinfunction "XCL_XCL") (pintype "bidirectional"))
    )
    (net (code "73") (name "unconnected-(U2-PadXDA)") (class "Default")
      (node (ref "U2") (pin "XDA") (pinfunction "XDA_XDA") (pintype "bidirectional"))
    )
  )
)
